# PackTemperatureSensor_-_v_1_0.net
KiCad netlist of a schematic drawn in EAGLE
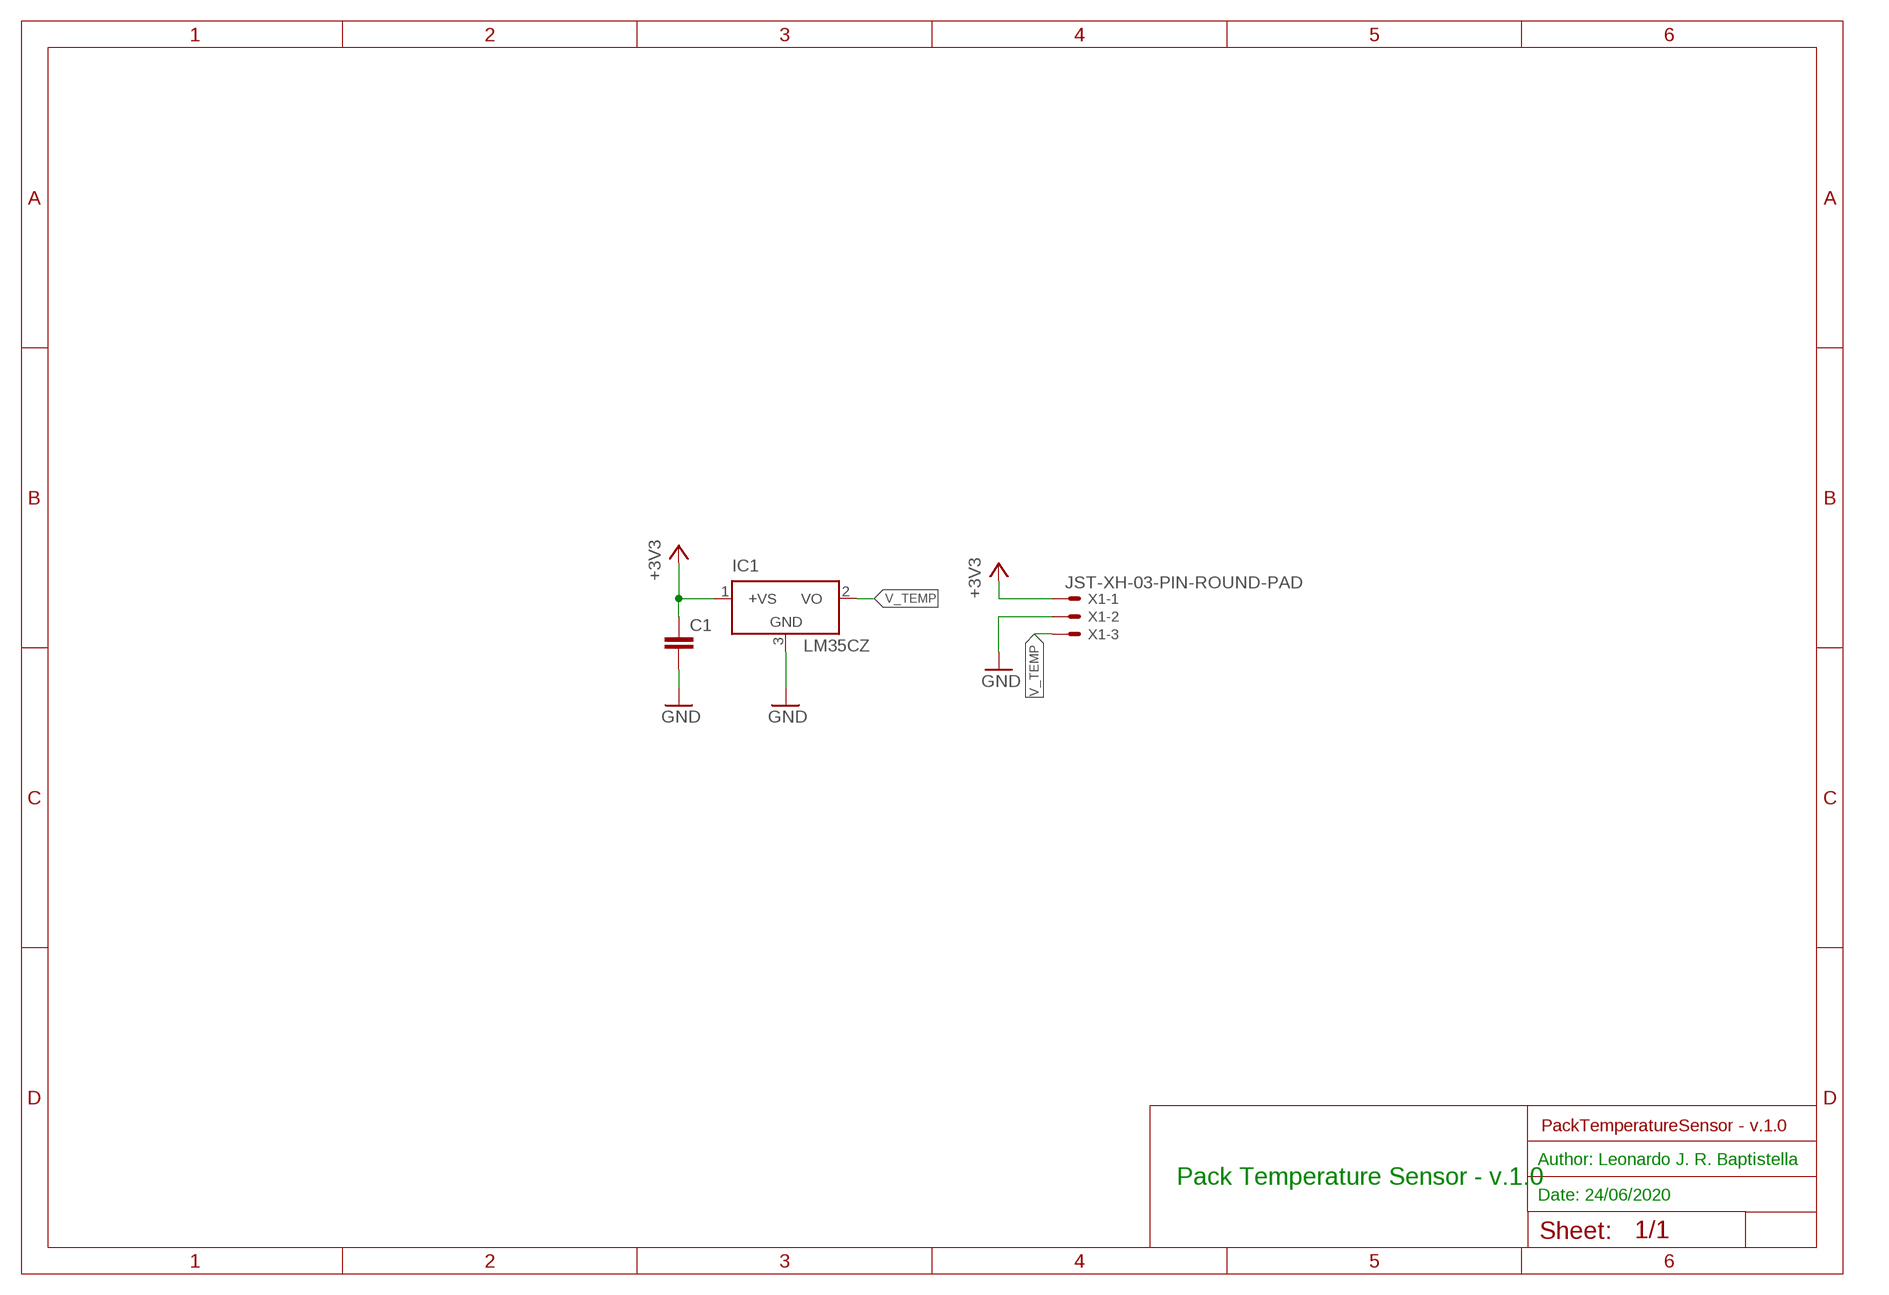
[diagram p0: schematic, sheet 1]

(export (version "E")
  (design (tool "Eeschema 10.0.6"))
  (components
    (comp (ref "C1")
      (value "C-EUC1206")
      (footprint "eagle-import:C1206")
      (libsource (lib "eagle-import") (part "C-EUC1206"))
    )
    (comp (ref "IC1")
      (value "LM35CZ")
      (footprint "eagle-import:TO92")
      (libsource (lib "eagle-import") (part "LM35CZ"))
    )
    (comp (ref "X1")
      (value "JST-XH-03-PIN-ROUND-PAD")
      (footprint "eagle-import:JST-XH-03-PACKAGE-ROUND-PAD")
      (libsource (lib "eagle-import") (part "JST-XH-03-PIN-ROUND-PAD"))
    )
  )
  (nets
    (net (code "1") (name "+3V3") (class "Default")
      (node (ref "C1") (pin "1") (pinfunction "1_1") (pintype "passive"))
      (node (ref "IC1") (pin "1") (pinfunction "+VS_1") (pintype "input"))
      (node (ref "X1") (pin "1") (pinfunction "S_1") (pintype "passive"))
    )
    (net (code "2") (name "GND") (class "Default")
      (node (ref "C1") (pin "2") (pinfunction "2_2") (pintype "passive"))
      (node (ref "IC1") (pin "3") (pinfunction "GND_3") (pintype "power_in"))
      (node (ref "X1") (pin "2") (pinfunction "S_2") (pintype "passive"))
    )
    (net (code "3") (name "V_TEMP") (class "Default")
      (node (ref "IC1") (pin "2") (pinfunction "VO_2") (pintype "input"))
      (node (ref "X1") (pin "3") (pinfunction "S_3") (pintype "passive"))
    )
  )
)
